# WaterDrop.net
KiCad netlist of a schematic drawn in EAGLE
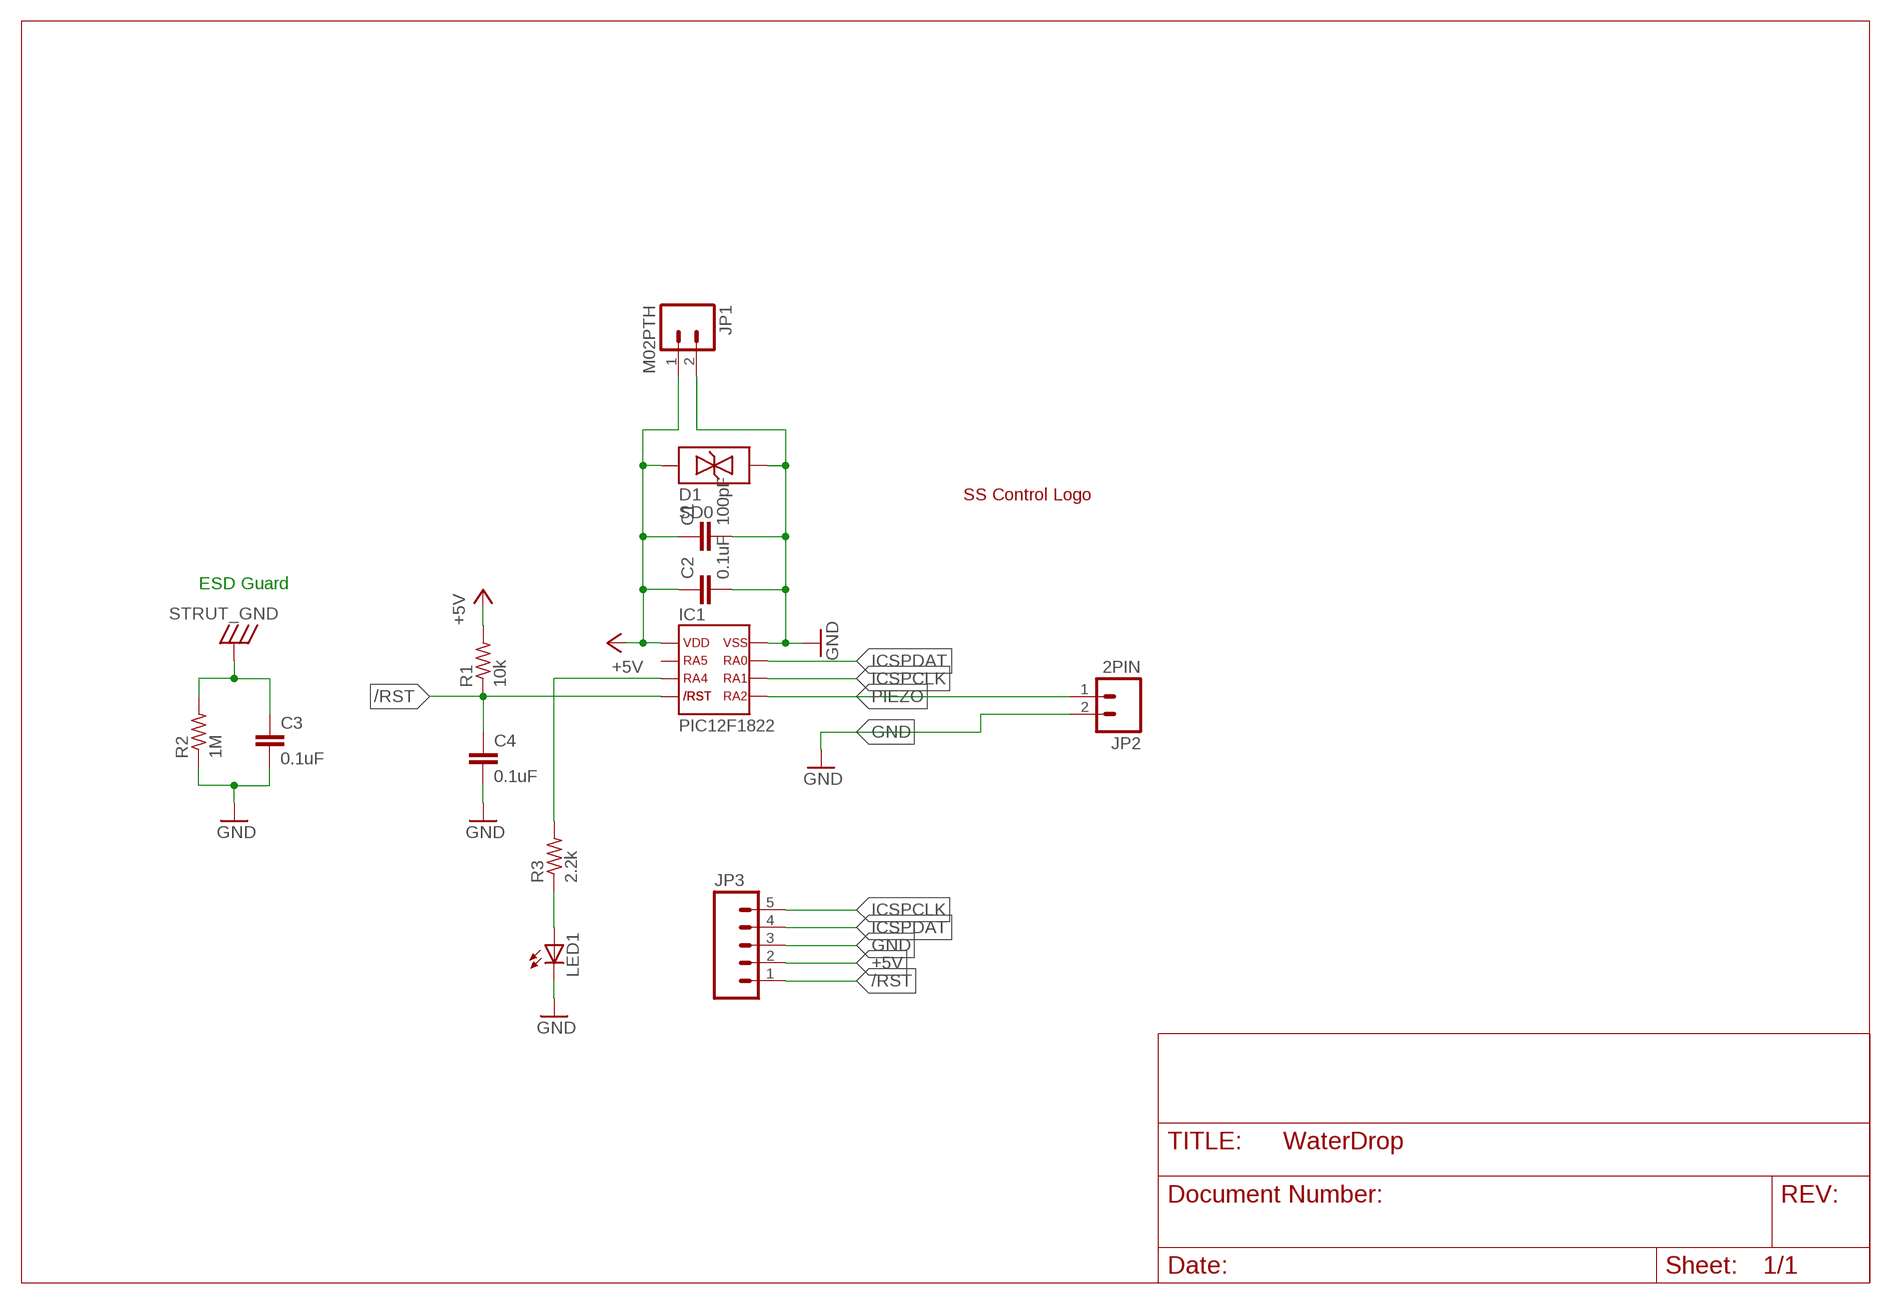
[diagram p0: schematic, sheet 1]

(export (version "E")
  (design (tool "Eeschema 10.0.6"))
  (components
    (comp (ref "C1")
      (value "100pF")
      (footprint "eagle-import:C0603(1608)")
      (libsource (lib "eagle-import") (part "C0603(1608)"))
    )
    (comp (ref "C2")
      (value "0.1uF")
      (footprint "eagle-import:C0603(1608)")
      (libsource (lib "eagle-import") (part "C0603(1608)"))
    )
    (comp (ref "C3")
      (value "0.1uF")
      (footprint "eagle-import:C0603(1608)")
      (libsource (lib "eagle-import") (part "C0603(1608)"))
    )
    (comp (ref "C4")
      (value "0.1uF")
      (footprint "eagle-import:C0603(1608)")
      (libsource (lib "eagle-import") (part "C0603(1608)"))
    )
    (comp (ref "D1")
      (value "SD0")
      (footprint "eagle-import:SOD-323")
      (libsource (lib "eagle-import") (part "SD0"))
    )
    (comp (ref "IC1")
      (value "PIC12F1822")
      (footprint "eagle-import:SO8")
      (libsource (lib "eagle-import") (part "PIC12F1822"))
    )
    (comp (ref "JP1")
      (value "M02PTH")
      (footprint "eagle-import:1X02")
      (libsource (lib "eagle-import") (part "M02PTH"))
    )
    (comp (ref "JP2")
      (value "2PIN")
      (footprint "eagle-import:2PIN5.08")
      (libsource (lib "eagle-import") (part "2PIN"))
    )
    (comp (ref "JP3")
      (value "M05PTH")
      (footprint "eagle-import:1X05")
      (libsource (lib "eagle-import") (part "M05PTH"))
    )
    (comp (ref "LED1")
      (value "LED0603")
      (footprint "eagle-import:LED-0603")
      (libsource (lib "eagle-import") (part "LED0603"))
    )
    (comp (ref "R1")
      (value "10k")
      (footprint "eagle-import:R0603(1608)")
      (libsource (lib "eagle-import") (part "R0603(1608)"))
    )
    (comp (ref "R2")
      (value "1M")
      (footprint "eagle-import:R0603(1608)")
      (libsource (lib "eagle-import") (part "R0603(1608)"))
    )
    (comp (ref "R3")
      (value "2.2k")
      (footprint "eagle-import:R0603(1608)")
      (libsource (lib "eagle-import") (part "R0603(1608)"))
    )
    (comp (ref "U$1")
      (value "LOGOPIEZO")
      (footprint "eagle-import:SSPIEZOLOGO")
      (libsource (lib "eagle-import") (part "LOGOPIEZO"))
    )
  )
  (nets
    (net (code "1") (name "+5V") (class "Default")
      (node (ref "C1") (pin "1") (pinfunction "1_1") (pintype "passive"))
      (node (ref "C2") (pin "1") (pinfunction "1_1") (pintype "passive"))
      (node (ref "D1") (pin "1") (pinfunction "P$1_1") (pintype "bidirectional"))
      (node (ref "IC1") (pin "1") (pinfunction "P$1_1") (pintype "power_in"))
      (node (ref "JP1") (pin "1") (pinfunction "1_1") (pintype "passive"))
      (node (ref "JP3") (pin "2") (pinfunction "2_2") (pintype "passive"))
      (node (ref "R1") (pin "2") (pinfunction "2_2") (pintype "passive"))
    )
    (net (code "2") (name "GND") (class "Default")
      (node (ref "C1") (pin "2") (pinfunction "2_2") (pintype "passive"))
      (node (ref "C2") (pin "2") (pinfunction "2_2") (pintype "passive"))
      (node (ref "C3") (pin "2") (pinfunction "2_2") (pintype "passive"))
      (node (ref "C4") (pin "2") (pinfunction "2_2") (pintype "passive"))
      (node (ref "D1") (pin "2") (pinfunction "P$2_2") (pintype "bidirectional"))
      (node (ref "IC1") (pin "8") (pinfunction "P$8_8") (pintype "power_in"))
      (node (ref "JP1") (pin "2") (pinfunction "2_2") (pintype "passive"))
      (node (ref "JP2") (pin "2") (pinfunction "2_2") (pintype "passive"))
      (node (ref "JP3") (pin "3") (pinfunction "3_3") (pintype "passive"))
      (node (ref "LED1") (pin "C") (pinfunction "C_C") (pintype "passive"))
      (node (ref "R2") (pin "1") (pinfunction "1_1") (pintype "passive"))
    )
    (net (code "3") (name "ICSPCLK") (class "Default")
      (node (ref "IC1") (pin "6") (pinfunction "P$6_6") (pintype "bidirectional"))
      (node (ref "JP3") (pin "5") (pinfunction "5_5") (pintype "passive"))
    )
    (net (code "4") (name "ICSPDAT") (class "Default")
      (node (ref "IC1") (pin "7") (pinfunction "P$7_7") (pintype "bidirectional"))
      (node (ref "JP3") (pin "4") (pinfunction "4_4") (pintype "passive"))
    )
    (net (code "5") (name "Net-(IC1-P$3)") (class "Default")
      (node (ref "IC1") (pin "3") (pinfunction "P$3_3") (pintype "bidirectional"))
      (node (ref "R3") (pin "2") (pinfunction "2_2") (pintype "passive"))
    )
    (net (code "6") (name "Net-(LED1-PadA)") (class "Default")
      (node (ref "LED1") (pin "A") (pinfunction "A_A") (pintype "passive"))
      (node (ref "R3") (pin "1") (pinfunction "1_1") (pintype "passive"))
    )
    (net (code "7") (name "PIEZO") (class "Default")
      (node (ref "IC1") (pin "5") (pinfunction "P$5_5") (pintype "bidirectional"))
      (node (ref "JP2") (pin "1") (pinfunction "1_1") (pintype "passive"))
    )
    (net (code "8") (name "STRUT_GND") (class "Default")
      (node (ref "C3") (pin "1") (pinfunction "1_1") (pintype "passive"))
      (node (ref "R2") (pin "2") (pinfunction "2_2") (pintype "passive"))
    )
    (net (code "9") (name "unconnected-(IC1-P$2-Pad2)") (class "Default")
      (node (ref "IC1") (pin "2") (pinfunction "P$2_2") (pintype "bidirectional"))
    )
    (net (code "10") (name "{slash}RST") (class "Default")
      (node (ref "C4") (pin "1") (pinfunction "1_1") (pintype "passive"))
      (node (ref "IC1") (pin "4") (pinfunction "P$4_4") (pintype "bidirectional"))
      (node (ref "JP3") (pin "1") (pinfunction "1_1") (pintype "passive"))
      (node (ref "R1") (pin "1") (pinfunction "1_1") (pintype "passive"))
    )
  )
)
